# Breathing_termo.net
KiCad netlist of a schematic drawn in EAGLE
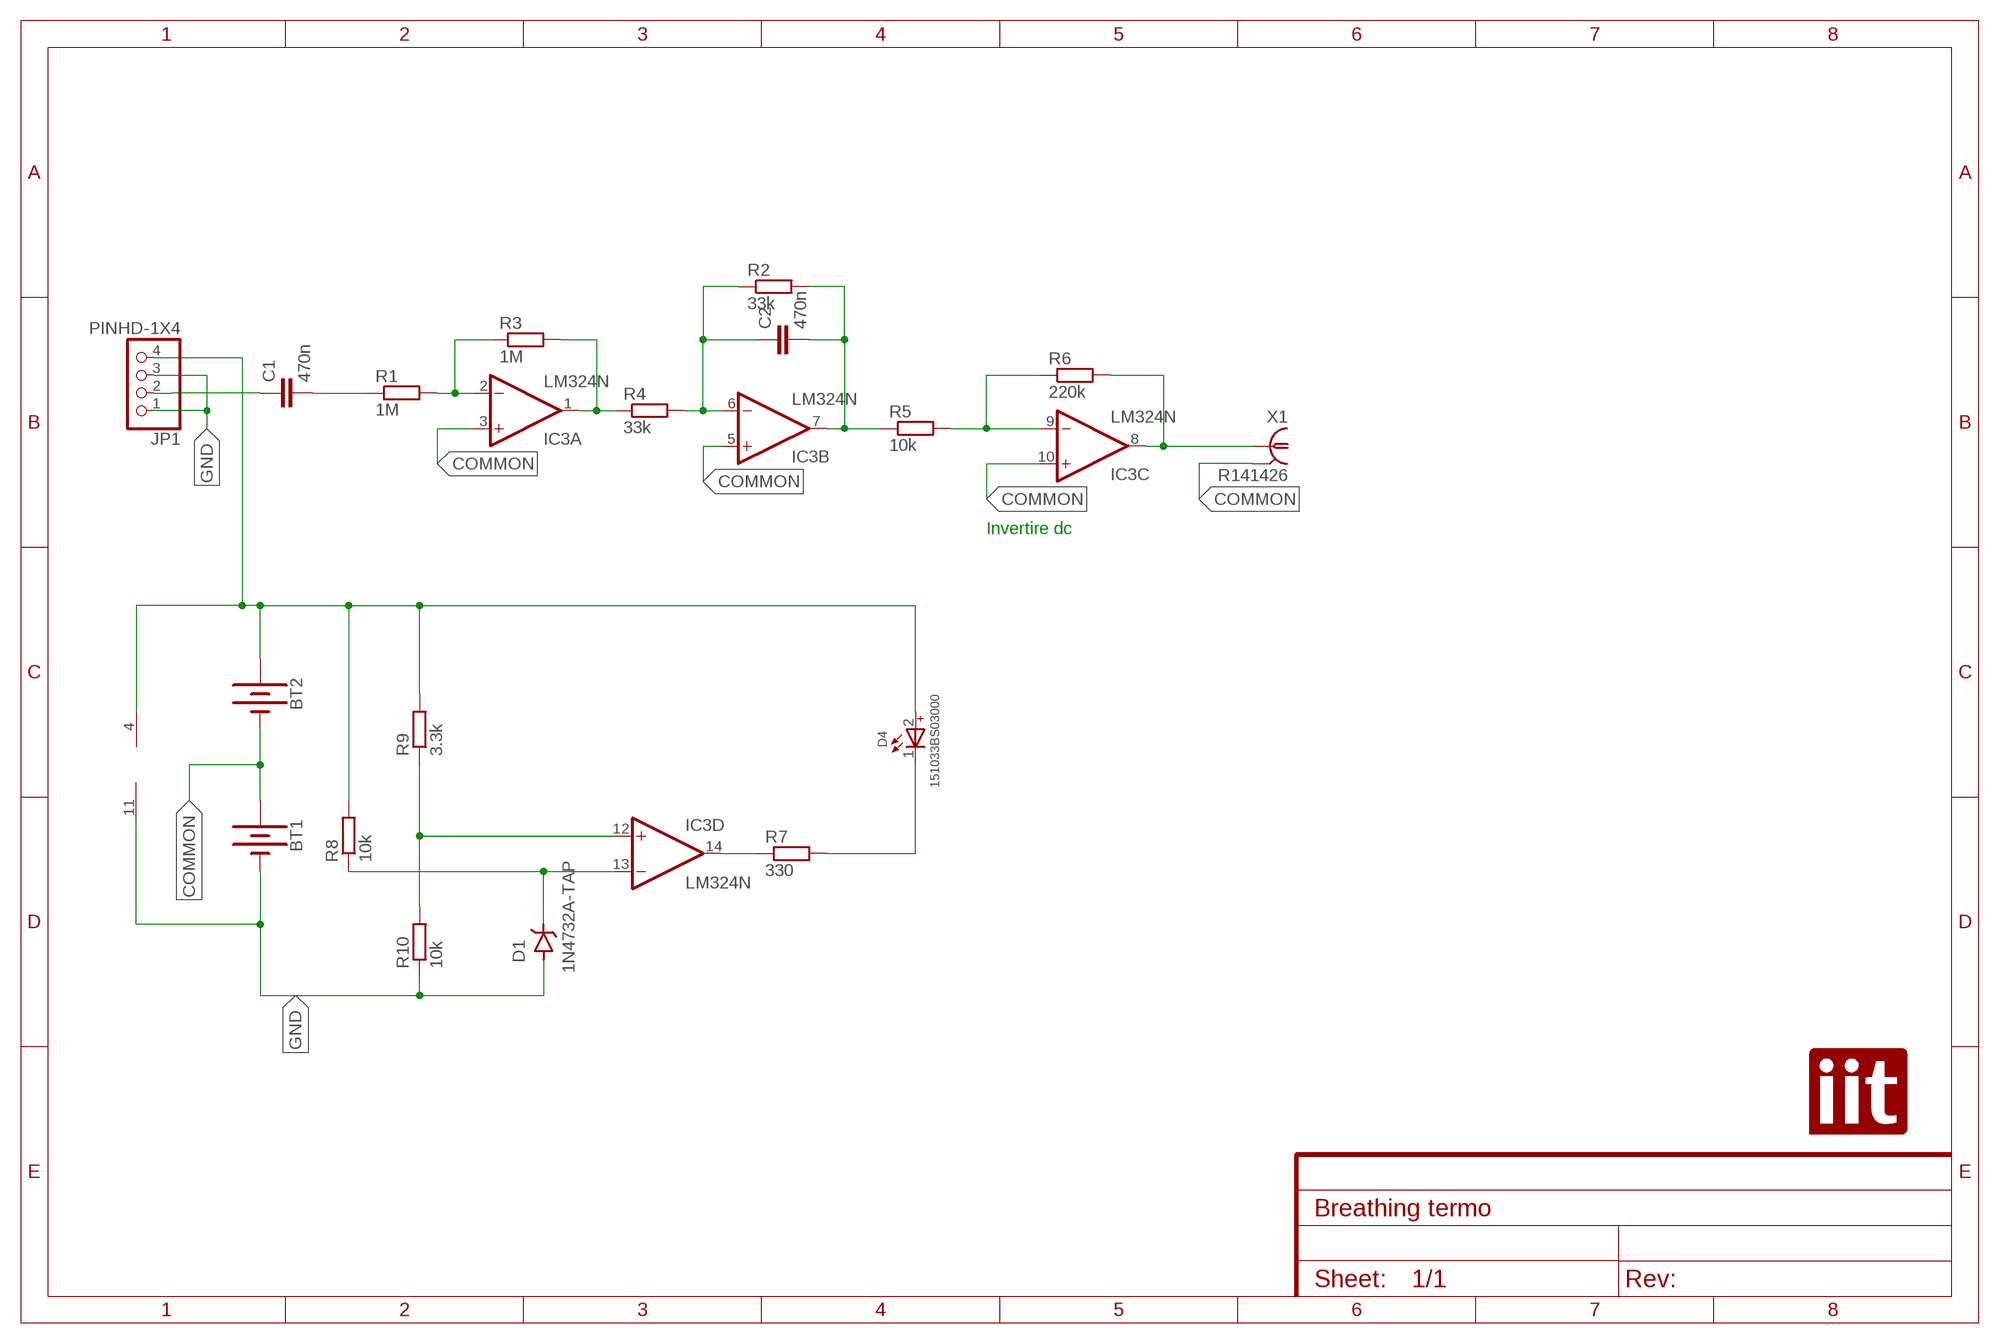
[diagram p0: schematic, sheet 1]

(export (version "E")
  (design (tool "Eeschema 10.0.6"))
  (components
    (comp (ref "BT1")
      (value "BATTERY-9V")
      (footprint "eagle-import:BATTCON_9V")
      (libsource (lib "eagle-import") (part "BATTERY-9V"))
    )
    (comp (ref "BT2")
      (value "BATTERY-9V")
      (footprint "eagle-import:BATTCON_9V")
      (libsource (lib "eagle-import") (part "BATTERY-9V"))
    )
    (comp (ref "C1")
      (value "470n")
      (footprint "eagle-import:C025-025X050")
      (libsource (lib "eagle-import") (part "C-EU025-025X050"))
    )
    (comp (ref "C2")
      (value "470n")
      (footprint "eagle-import:C025-025X050")
      (libsource (lib "eagle-import") (part "C-EU025-025X050"))
    )
    (comp (ref "D1")
      (value "1N4732A-TAP")
      (footprint "eagle-import:DO-41")
      (fields
        (field (name "DIGIKEY_PART_NUMBER") "1N4732A-TAPGICT-ND")
        (field (name "MANUFACTURER") "Vishay General Semiconductor - Diodes Division")
        (field (name "CREATED_BY") "PCBLayout.com")
      )
      (libsource (lib "eagle-import") (part "1N4732A-TAP"))
    )
    (comp (ref "D4")
      (value "151033BS03000")
      (footprint "eagle-import:WL-TMRW_3MM_STOPPER")
      (libsource (lib "eagle-import") (part "WL-TMRW_3MM_WITHSTOPPER_151033BS03000"))
    )
    (comp (ref "IC3")
      (value "LM324N")
      (footprint "eagle-import:DIL14")
      (libsource (lib "eagle-import") (part "LM324N"))
    )
    (comp (ref "JP1")
      (value "PINHD-1X4")
      (footprint "eagle-import:1X04")
      (fields (field (name "MANUFACTURER") "Generic"))
      (libsource (lib "eagle-import") (part "PINHD-1X4"))
    )
    (comp (ref "R1")
      (value "1M")
      (footprint "eagle-import:0204_7")
      (libsource (lib "eagle-import") (part "R-EU_0204/7"))
    )
    (comp (ref "R2")
      (value "33k")
      (footprint "eagle-import:0204_7")
      (libsource (lib "eagle-import") (part "R-EU_0204/7"))
    )
    (comp (ref "R3")
      (value "1M")
      (footprint "eagle-import:0204_7")
      (libsource (lib "eagle-import") (part "R-EU_0204/7"))
    )
    (comp (ref "R4")
      (value "33k")
      (footprint "eagle-import:0204_7")
      (libsource (lib "eagle-import") (part "R-EU_0204/7"))
    )
    (comp (ref "R5")
      (value "10k")
      (footprint "eagle-import:0204_7")
      (libsource (lib "eagle-import") (part "R-EU_0204/7"))
    )
    (comp (ref "R6")
      (value "220k")
      (footprint "eagle-import:0204_7")
      (libsource (lib "eagle-import") (part "R-EU_0204/7"))
    )
    (comp (ref "R7")
      (value "330")
      (footprint "eagle-import:0204_7")
      (libsource (lib "eagle-import") (part "R-EU_0204/7"))
    )
    (comp (ref "R8")
      (value "10k")
      (footprint "eagle-import:0204_7")
      (libsource (lib "eagle-import") (part "R-EU_0204/7"))
    )
    (comp (ref "R9")
      (value "3.3k")
      (footprint "eagle-import:0204_7")
      (libsource (lib "eagle-import") (part "R-EU_0204/7"))
    )
    (comp (ref "R10")
      (value "10k")
      (footprint "eagle-import:0204_7")
      (libsource (lib "eagle-import") (part "R-EU_0204/7"))
    )
    (comp (ref "U$1")
      (value "LOGO")
      (footprint "eagle-import:IIT")
      (libsource (lib "eagle-import") (part "LOGO"))
    )
    (comp (ref "X1")
      (value "R141426")
      (footprint "eagle-import:R141426")
      (fields (field (name "MF") "FARNELL") (field (name "MPN") "R141426161"))
      (libsource (lib "eagle-import") (part "R141426"))
    )
  )
  (nets
    (net (code "1") (name "COMMON") (class "Default")
      (node (ref "BT1") (pin "+") (pinfunction "+_+") (pintype "power_in"))
      (node (ref "BT2") (pin "-") (pinfunction "-_-") (pintype "power_in"))
      (node (ref "IC3") (pin "10") (pinfunction "+IN_10") (pintype "input"))
      (node (ref "IC3") (pin "3") (pinfunction "+IN_3") (pintype "input"))
      (node (ref "IC3") (pin "5") (pinfunction "+IN_5") (pintype "input"))
      (node (ref "X1") (pin "2") (pinfunction "2_2") (pintype "passive"))
      (node (ref "X1") (pin "3") (pinfunction "2_3") (pintype "passive"))
      (node (ref "X1") (pin "4") (pinfunction "2_4") (pintype "passive"))
      (node (ref "X1") (pin "5") (pinfunction "2_5") (pintype "passive"))
    )
    (net (code "2") (name "GND") (class "Default")
      (node (ref "BT1") (pin "-") (pinfunction "-_-") (pintype "power_in"))
      (node (ref "D1") (pin "A") (pinfunction "A_A") (pintype "passive"))
      (node (ref "IC3") (pin "11") (pinfunction "V-_11") (pintype "power_in"))
      (node (ref "JP1") (pin "1") (pinfunction "1_1") (pintype "passive"))
      (node (ref "JP1") (pin "3") (pinfunction "3_3") (pintype "passive"))
      (node (ref "R10") (pin "1") (pinfunction "1_1") (pintype "passive"))
    )
    (net (code "3") (name "Net-(C1-Pad1)") (class "Default")
      (node (ref "C1") (pin "1") (pinfunction "1_1") (pintype "passive"))
      (node (ref "JP1") (pin "2") (pinfunction "2_2") (pintype "passive"))
    )
    (net (code "4") (name "Net-(C1-Pad2)") (class "Default")
      (node (ref "C1") (pin "2") (pinfunction "2_2") (pintype "passive"))
      (node (ref "R1") (pin "1") (pinfunction "1_1") (pintype "passive"))
    )
    (net (code "5") (name "Net-(D4-+)") (class "Default")
      (node (ref "BT2") (pin "+") (pinfunction "+_+") (pintype "power_in"))
      (node (ref "D4") (pin "2") (pinfunction "+_2") (pintype "passive"))
      (node (ref "IC3") (pin "4") (pinfunction "V+_4") (pintype "power_in"))
      (node (ref "JP1") (pin "4") (pinfunction "4_4") (pintype "passive"))
      (node (ref "R8") (pin "2") (pinfunction "2_2") (pintype "passive"))
      (node (ref "R9") (pin "2") (pinfunction "2_2") (pintype "passive"))
    )
    (net (code "6") (name "Net-(D4--)") (class "Default")
      (node (ref "D4") (pin "1") (pinfunction "-_1") (pintype "passive"))
      (node (ref "R7") (pin "2") (pinfunction "2_2") (pintype "passive"))
    )
    (net (code "7") (name "Net-(IC3A--IN)") (class "Default")
      (node (ref "IC3") (pin "2") (pinfunction "-IN_2") (pintype "input"))
      (node (ref "R1") (pin "2") (pinfunction "2_2") (pintype "passive"))
      (node (ref "R3") (pin "1") (pinfunction "1_1") (pintype "passive"))
    )
    (net (code "8") (name "Net-(IC3A-OUT)") (class "Default")
      (node (ref "IC3") (pin "1") (pinfunction "OUT_1") (pintype "output"))
      (node (ref "R3") (pin "2") (pinfunction "2_2") (pintype "passive"))
      (node (ref "R4") (pin "1") (pinfunction "1_1") (pintype "passive"))
    )
    (net (code "9") (name "Net-(IC3B--IN)") (class "Default")
      (node (ref "C2") (pin "1") (pinfunction "1_1") (pintype "passive"))
      (node (ref "IC3") (pin "6") (pinfunction "-IN_6") (pintype "input"))
      (node (ref "R2") (pin "1") (pinfunction "1_1") (pintype "passive"))
      (node (ref "R4") (pin "2") (pinfunction "2_2") (pintype "passive"))
    )
    (net (code "10") (name "Net-(IC3B-OUT)") (class "Default")
      (node (ref "C2") (pin "2") (pinfunction "2_2") (pintype "passive"))
      (node (ref "IC3") (pin "7") (pinfunction "OUT_7") (pintype "output"))
      (node (ref "R2") (pin "2") (pinfunction "2_2") (pintype "passive"))
      (node (ref "R5") (pin "1") (pinfunction "1_1") (pintype "passive"))
    )
    (net (code "11") (name "Net-(IC3C--IN)") (class "Default")
      (node (ref "IC3") (pin "9") (pinfunction "-IN_9") (pintype "input"))
      (node (ref "R5") (pin "2") (pinfunction "2_2") (pintype "passive"))
      (node (ref "R6") (pin "1") (pinfunction "1_1") (pintype "passive"))
    )
    (net (code "12") (name "Net-(IC3C-OUT)") (class "Default")
      (node (ref "IC3") (pin "8") (pinfunction "OUT_8") (pintype "output"))
      (node (ref "R6") (pin "2") (pinfunction "2_2") (pintype "passive"))
      (node (ref "X1") (pin "1") (pinfunction "1_1") (pintype "passive"))
    )
    (net (code "13") (name "Net-(IC3D-+IN)") (class "Default")
      (node (ref "IC3") (pin "12") (pinfunction "+IN_12") (pintype "input"))
      (node (ref "R10") (pin "2") (pinfunction "2_2") (pintype "passive"))
      (node (ref "R9") (pin "1") (pinfunction "1_1") (pintype "passive"))
    )
    (net (code "14") (name "Net-(IC3D--IN)") (class "Default")
      (node (ref "D1") (pin "C") (pinfunction "C_C") (pintype "passive"))
      (node (ref "IC3") (pin "13") (pinfunction "-IN_13") (pintype "input"))
      (node (ref "R8") (pin "1") (pinfunction "1_1") (pintype "passive"))
    )
    (net (code "15") (name "Net-(IC3D-OUT)") (class "Default")
      (node (ref "IC3") (pin "14") (pinfunction "OUT_14") (pintype "output"))
      (node (ref "R7") (pin "1") (pinfunction "1_1") (pintype "passive"))
    )
  )
)
